# pneuBoard_rev3.net
KiCad netlist of a schematic drawn in EAGLE
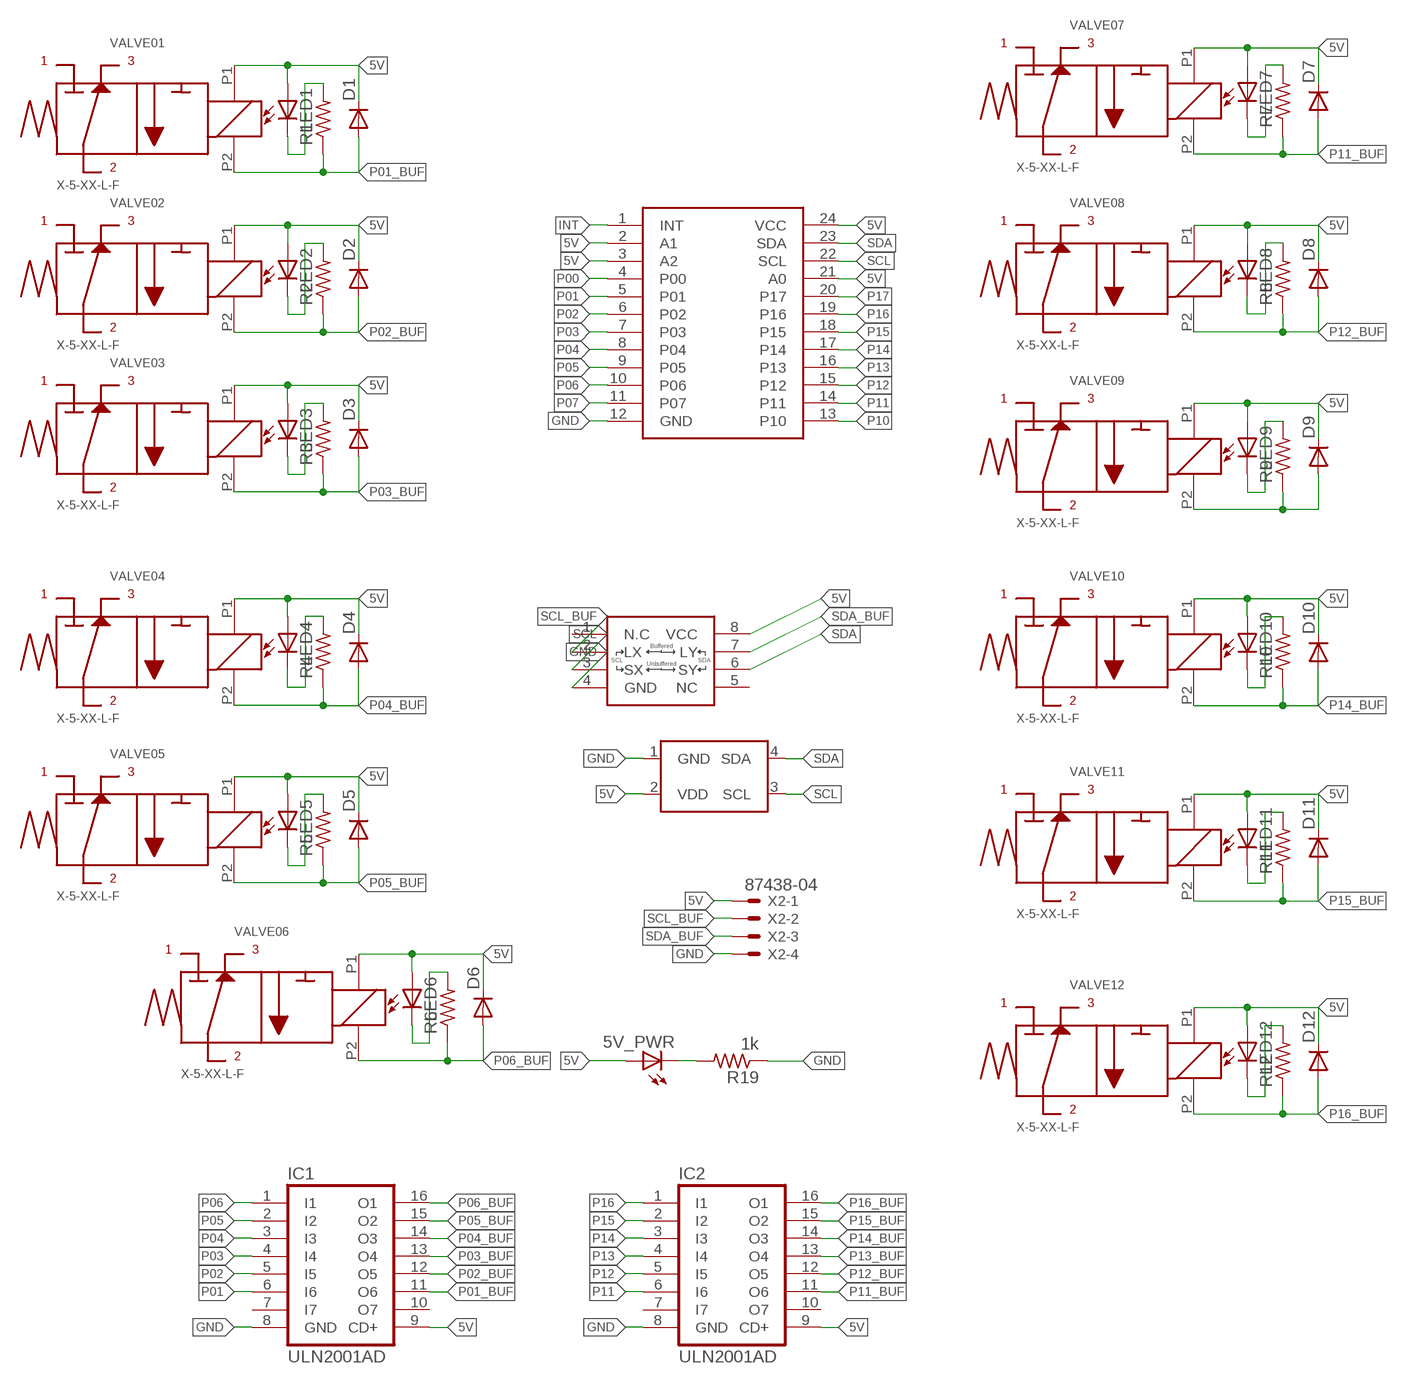
[diagram p0: schematic, sheet 1]

(export (version "E")
  (design (tool "Eeschema 10.0.6"))
  (components
    (comp (ref "5V_PWR")
      (value "LEDSML1206")
      (footprint "eagle-import:SML1206")
      (libsource (lib "eagle-import") (part "LEDSML1206"))
    )
    (comp (ref "D1")
      (value "DIODE-SOD123")
      (footprint "eagle-import:SOD123")
      (libsource (lib "eagle-import") (part "DIODE-SOD123"))
    )
    (comp (ref "D2")
      (value "DIODE-SOD123")
      (footprint "eagle-import:SOD123")
      (libsource (lib "eagle-import") (part "DIODE-SOD123"))
    )
    (comp (ref "D3")
      (value "DIODE-SOD123")
      (footprint "eagle-import:SOD123")
      (libsource (lib "eagle-import") (part "DIODE-SOD123"))
    )
    (comp (ref "D4")
      (value "DIODE-SOD123")
      (footprint "eagle-import:SOD123")
      (libsource (lib "eagle-import") (part "DIODE-SOD123"))
    )
    (comp (ref "D5")
      (value "DIODE-SOD123")
      (footprint "eagle-import:SOD123")
      (libsource (lib "eagle-import") (part "DIODE-SOD123"))
    )
    (comp (ref "D6")
      (value "DIODE-SOD123")
      (footprint "eagle-import:SOD123")
      (libsource (lib "eagle-import") (part "DIODE-SOD123"))
    )
    (comp (ref "D7")
      (value "DIODE-SOD123")
      (footprint "eagle-import:SOD123")
      (libsource (lib "eagle-import") (part "DIODE-SOD123"))
    )
    (comp (ref "D8")
      (value "DIODE-SOD123")
      (footprint "eagle-import:SOD123")
      (libsource (lib "eagle-import") (part "DIODE-SOD123"))
    )
    (comp (ref "D9")
      (value "DIODE-SOD123")
      (footprint "eagle-import:SOD123")
      (libsource (lib "eagle-import") (part "DIODE-SOD123"))
    )
    (comp (ref "D10")
      (value "DIODE-SOD123")
      (footprint "eagle-import:SOD123")
      (libsource (lib "eagle-import") (part "DIODE-SOD123"))
    )
    (comp (ref "D11")
      (value "DIODE-SOD123")
      (footprint "eagle-import:SOD123")
      (libsource (lib "eagle-import") (part "DIODE-SOD123"))
    )
    (comp (ref "D12")
      (value "DIODE-SOD123")
      (footprint "eagle-import:SOD123")
      (libsource (lib "eagle-import") (part "DIODE-SOD123"))
    )
    (comp (ref "IC1")
      (value "ULN2001AD")
      (footprint "eagle-import:SO16")
      (libsource (lib "eagle-import") (part "ULN2001AD"))
    )
    (comp (ref "IC2")
      (value "ULN2001AD")
      (footprint "eagle-import:SO16")
      (libsource (lib "eagle-import") (part "ULN2001AD"))
    )
    (comp (ref "LED1")
      (value "LEDCHIPLED_1206")
      (footprint "eagle-import:CHIPLED_1206")
      (libsource (lib "eagle-import") (part "LEDCHIPLED_1206"))
    )
    (comp (ref "LED2")
      (value "LEDCHIPLED_1206")
      (footprint "eagle-import:CHIPLED_1206")
      (libsource (lib "eagle-import") (part "LEDCHIPLED_1206"))
    )
    (comp (ref "LED3")
      (value "LEDCHIPLED_1206")
      (footprint "eagle-import:CHIPLED_1206")
      (libsource (lib "eagle-import") (part "LEDCHIPLED_1206"))
    )
    (comp (ref "LED4")
      (value "LEDCHIPLED_1206")
      (footprint "eagle-import:CHIPLED_1206")
      (libsource (lib "eagle-import") (part "LEDCHIPLED_1206"))
    )
    (comp (ref "LED5")
      (value "LEDCHIPLED_1206")
      (footprint "eagle-import:CHIPLED_1206")
      (libsource (lib "eagle-import") (part "LEDCHIPLED_1206"))
    )
    (comp (ref "LED6")
      (value "LEDCHIPLED_1206")
      (footprint "eagle-import:CHIPLED_1206")
      (libsource (lib "eagle-import") (part "LEDCHIPLED_1206"))
    )
    (comp (ref "LED7")
      (value "LEDCHIPLED_1206")
      (footprint "eagle-import:CHIPLED_1206")
      (libsource (lib "eagle-import") (part "LEDCHIPLED_1206"))
    )
    (comp (ref "LED8")
      (value "LEDCHIPLED_1206")
      (footprint "eagle-import:CHIPLED_1206")
      (libsource (lib "eagle-import") (part "LEDCHIPLED_1206"))
    )
    (comp (ref "LED9")
      (value "LEDCHIPLED_1206")
      (footprint "eagle-import:CHIPLED_1206")
      (libsource (lib "eagle-import") (part "LEDCHIPLED_1206"))
    )
    (comp (ref "LED10")
      (value "LEDCHIPLED_1206")
      (footprint "eagle-import:CHIPLED_1206")
      (libsource (lib "eagle-import") (part "LEDCHIPLED_1206"))
    )
    (comp (ref "LED11")
      (value "LEDCHIPLED_1206")
      (footprint "eagle-import:CHIPLED_1206")
      (libsource (lib "eagle-import") (part "LEDCHIPLED_1206"))
    )
    (comp (ref "LED12")
      (value "LEDCHIPLED_1206")
      (footprint "eagle-import:CHIPLED_1206")
      (libsource (lib "eagle-import") (part "LEDCHIPLED_1206"))
    )
    (comp (ref "R1")
      (value "R-US_R0603")
      (footprint "eagle-import:R0603")
      (libsource (lib "eagle-import") (part "R-US_R0603"))
    )
    (comp (ref "R2")
      (value "R-US_R0603")
      (footprint "eagle-import:R0603")
      (libsource (lib "eagle-import") (part "R-US_R0603"))
    )
    (comp (ref "R3")
      (value "R-US_R0603")
      (footprint "eagle-import:R0603")
      (libsource (lib "eagle-import") (part "R-US_R0603"))
    )
    (comp (ref "R4")
      (value "R-US_R0603")
      (footprint "eagle-import:R0603")
      (libsource (lib "eagle-import") (part "R-US_R0603"))
    )
    (comp (ref "R5")
      (value "R-US_R0603")
      (footprint "eagle-import:R0603")
      (libsource (lib "eagle-import") (part "R-US_R0603"))
    )
    (comp (ref "R6")
      (value "R-US_R0603")
      (footprint "eagle-import:R0603")
      (libsource (lib "eagle-import") (part "R-US_R0603"))
    )
    (comp (ref "R7")
      (value "R-US_R0603")
      (footprint "eagle-import:R0603")
      (libsource (lib "eagle-import") (part "R-US_R0603"))
    )
    (comp (ref "R8")
      (value "R-US_R0603")
      (footprint "eagle-import:R0603")
      (libsource (lib "eagle-import") (part "R-US_R0603"))
    )
    (comp (ref "R9")
      (value "R-US_R0603")
      (footprint "eagle-import:R0603")
      (libsource (lib "eagle-import") (part "R-US_R0603"))
    )
    (comp (ref "R10")
      (value "R-US_R0603")
      (footprint "eagle-import:R0603")
      (libsource (lib "eagle-import") (part "R-US_R0603"))
    )
    (comp (ref "R11")
      (value "R-US_R0603")
      (footprint "eagle-import:R0603")
      (libsource (lib "eagle-import") (part "R-US_R0603"))
    )
    (comp (ref "R12")
      (value "R-US_R0603")
      (footprint "eagle-import:R0603")
      (libsource (lib "eagle-import") (part "R-US_R0603"))
    )
    (comp (ref "R19")
      (value "1k")
      (footprint "eagle-import:R0603")
      (libsource (lib "eagle-import") (part "R-US_R0603"))
    )
    (comp (ref "U$1")
      (value "PCF8575C")
      (footprint "eagle-import:PW_R-PDSO-G24")
      (libsource (lib "eagle-import") (part "PCF8575C"))
    )
    (comp (ref "U$2")
      (value "P82B715")
      (footprint "eagle-import:SO8")
      (libsource (lib "eagle-import") (part "P82B715"))
    )
    (comp (ref "U$3")
      (value "MS5837-30BA")
      (footprint "eagle-import:MS5837-30BA")
      (libsource (lib "eagle-import") (part "MS5837-30BA"))
    )
    (comp (ref "VALVE01")
      (value "X-5-XX-L-F")
      (footprint "eagle-import:X-SERIES")
      (libsource (lib "eagle-import") (part "X-5-XX-L-F"))
    )
    (comp (ref "VALVE02")
      (value "X-5-XX-L-F")
      (footprint "eagle-import:X-SERIES")
      (libsource (lib "eagle-import") (part "X-5-XX-L-F"))
    )
    (comp (ref "VALVE03")
      (value "X-5-XX-L-F")
      (footprint "eagle-import:X-SERIES")
      (libsource (lib "eagle-import") (part "X-5-XX-L-F"))
    )
    (comp (ref "VALVE04")
      (value "X-5-XX-L-F")
      (footprint "eagle-import:X-SERIES")
      (libsource (lib "eagle-import") (part "X-5-XX-L-F"))
    )
    (comp (ref "VALVE05")
      (value "X-5-XX-L-F")
      (footprint "eagle-import:X-SERIES")
      (libsource (lib "eagle-import") (part "X-5-XX-L-F"))
    )
    (comp (ref "VALVE06")
      (value "X-5-XX-L-F")
      (footprint "eagle-import:X-SERIES")
      (libsource (lib "eagle-import") (part "X-5-XX-L-F"))
    )
    (comp (ref "VALVE07")
      (value "X-5-XX-L-F")
      (footprint "eagle-import:X-SERIES")
      (libsource (lib "eagle-import") (part "X-5-XX-L-F"))
    )
    (comp (ref "VALVE08")
      (value "X-5-XX-L-F")
      (footprint "eagle-import:X-SERIES")
      (libsource (lib "eagle-import") (part "X-5-XX-L-F"))
    )
    (comp (ref "VALVE09")
      (value "X-5-XX-L-F")
      (footprint "eagle-import:X-SERIES")
      (libsource (lib "eagle-import") (part "X-5-XX-L-F"))
    )
    (comp (ref "VALVE10")
      (value "X-5-XX-L-F")
      (footprint "eagle-import:X-SERIES")
      (libsource (lib "eagle-import") (part "X-5-XX-L-F"))
    )
    (comp (ref "VALVE11")
      (value "X-5-XX-L-F")
      (footprint "eagle-import:X-SERIES")
      (libsource (lib "eagle-import") (part "X-5-XX-L-F"))
    )
    (comp (ref "VALVE12")
      (value "X-5-XX-L-F")
      (footprint "eagle-import:X-SERIES")
      (libsource (lib "eagle-import") (part "X-5-XX-L-F"))
    )
    (comp (ref "X2")
      (value "87438-04")
      (footprint "eagle-import:87438-04")
      (libsource (lib "eagle-import") (part "87438-04"))
    )
  )
  (nets
    (net (code "1") (name "5V") (class "Default")
      (node (ref "5V_PWR") (pin "A") (pinfunction "A_A") (pintype "passive"))
      (node (ref "D1") (pin "C") (pinfunction "C_C") (pintype "passive"))
      (node (ref "D10") (pin "C") (pinfunction "C_C") (pintype "passive"))
      (node (ref "D11") (pin "C") (pinfunction "C_C") (pintype "passive"))
      (node (ref "D12") (pin "C") (pinfunction "C_C") (pintype "passive"))
      (node (ref "D2") (pin "C") (pinfunction "C_C") (pintype "passive"))
      (node (ref "D3") (pin "C") (pinfunction "C_C") (pintype "passive"))
      (node (ref "D4") (pin "C") (pinfunction "C_C") (pintype "passive"))
      (node (ref "D5") (pin "C") (pinfunction "C_C") (pintype "passive"))
      (node (ref "D6") (pin "C") (pinfunction "C_C") (pintype "passive"))
      (node (ref "D7") (pin "C") (pinfunction "C_C") (pintype "passive"))
      (node (ref "D8") (pin "C") (pinfunction "C_C") (pintype "passive"))
      (node (ref "D9") (pin "C") (pinfunction "C_C") (pintype "passive"))
      (node (ref "IC1") (pin "9") (pinfunction "CD+_9") (pintype "passive"))
      (node (ref "IC2") (pin "9") (pinfunction "CD+_9") (pintype "passive"))
      (node (ref "LED1") (pin "A") (pinfunction "A_A") (pintype "passive"))
      (node (ref "LED10") (pin "A") (pinfunction "A_A") (pintype "passive"))
      (node (ref "LED11") (pin "A") (pinfunction "A_A") (pintype "passive"))
      (node (ref "LED12") (pin "A") (pinfunction "A_A") (pintype "passive"))
      (node (ref "LED2") (pin "A") (pinfunction "A_A") (pintype "passive"))
      (node (ref "LED3") (pin "A") (pinfunction "A_A") (pintype "passive"))
      (node (ref "LED4") (pin "A") (pinfunction "A_A") (pintype "passive"))
      (node (ref "LED5") (pin "A") (pinfunction "A_A") (pintype "passive"))
      (node (ref "LED6") (pin "A") (pinfunction "A_A") (pintype "passive"))
      (node (ref "LED7") (pin "A") (pinfunction "A_A") (pintype "passive"))
      (node (ref "LED8") (pin "A") (pinfunction "A_A") (pintype "passive"))
      (node (ref "LED9") (pin "A") (pinfunction "A_A") (pintype "passive"))
      (node (ref "U$1") (pin "2") (pinfunction "A1_2") (pintype "bidirectional"))
      (node (ref "U$1") (pin "21") (pinfunction "A0_21") (pintype "bidirectional"))
      (node (ref "U$1") (pin "24") (pinfunction "VCC_24") (pintype "bidirectional"))
      (node (ref "U$1") (pin "3") (pinfunction "A2_3") (pintype "bidirectional"))
      (node (ref "U$2") (pin "8") (pinfunction "VCC_8") (pintype "bidirectional"))
      (node (ref "U$3") (pin "2") (pinfunction "VDD_2") (pintype "bidirectional"))
      (node (ref "VALVE01") (pin "P1") (pinfunction "1_P1") (pintype "bidirectional"))
      (node (ref "VALVE02") (pin "P1") (pinfunction "1_P1") (pintype "bidirectional"))
      (node (ref "VALVE03") (pin "P1") (pinfunction "1_P1") (pintype "bidirectional"))
      (node (ref "VALVE04") (pin "P1") (pinfunction "1_P1") (pintype "bidirectional"))
      (node (ref "VALVE05") (pin "P1") (pinfunction "1_P1") (pintype "bidirectional"))
      (node (ref "VALVE06") (pin "P1") (pinfunction "1_P1") (pintype "bidirectional"))
      (node (ref "VALVE07") (pin "P1") (pinfunction "1_P1") (pintype "bidirectional"))
      (node (ref "VALVE08") (pin "P1") (pinfunction "1_P1") (pintype "bidirectional"))
      (node (ref "VALVE09") (pin "P1") (pinfunction "1_P1") (pintype "bidirectional"))
      (node (ref "VALVE10") (pin "P1") (pinfunction "1_P1") (pintype "bidirectional"))
      (node (ref "VALVE11") (pin "P1") (pinfunction "1_P1") (pintype "bidirectional"))
      (node (ref "VALVE12") (pin "P1") (pinfunction "1_P1") (pintype "bidirectional"))
      (node (ref "X2") (pin "1") (pinfunction "S_1") (pintype "passive"))
    )
    (net (code "2") (name "GND") (class "Default")
      (node (ref "IC1") (pin "8") (pinfunction "GND_8") (pintype "power_in"))
      (node (ref "IC2") (pin "8") (pinfunction "GND_8") (pintype "power_in"))
      (node (ref "R19") (pin "1") (pinfunction "1_1") (pintype "passive"))
      (node (ref "U$1") (pin "12") (pinfunction "GND_12") (pintype "bidirectional"))
      (node (ref "U$2") (pin "4") (pinfunction "GND_4") (pintype "bidirectional"))
      (node (ref "U$3") (pin "1") (pinfunction "GND_1") (pintype "bidirectional"))
      (node (ref "X2") (pin "4") (pinfunction "S_4") (pintype "passive"))
    )
    (net (code "3") (name "INT") (class "Default")
      (node (ref "U$1") (pin "1") (pinfunction "INT_1") (pintype "bidirectional"))
    )
    (net (code "4") (name "Net-(5V_PWR-PadC)") (class "Default")
      (node (ref "5V_PWR") (pin "C") (pinfunction "C_C") (pintype "passive"))
      (node (ref "R19") (pin "2") (pinfunction "2_2") (pintype "passive"))
    )
    (net (code "5") (name "Net-(LED1-PadC)") (class "Default")
      (node (ref "LED1") (pin "C") (pinfunction "C_C") (pintype "passive"))
      (node (ref "R1") (pin "2") (pinfunction "2_2") (pintype "passive"))
    )
    (net (code "6") (name "Net-(LED2-PadC)") (class "Default")
      (node (ref "LED2") (pin "C") (pinfunction "C_C") (pintype "passive"))
      (node (ref "R2") (pin "2") (pinfunction "2_2") (pintype "passive"))
    )
    (net (code "7") (name "Net-(LED3-PadC)") (class "Default")
      (node (ref "LED3") (pin "C") (pinfunction "C_C") (pintype "passive"))
      (node (ref "R3") (pin "2") (pinfunction "2_2") (pintype "passive"))
    )
    (net (code "8") (name "Net-(LED4-PadC)") (class "Default")
      (node (ref "LED4") (pin "C") (pinfunction "C_C") (pintype "passive"))
      (node (ref "R4") (pin "2") (pinfunction "2_2") (pintype "passive"))
    )
    (net (code "9") (name "Net-(LED5-PadC)") (class "Default")
      (node (ref "LED5") (pin "C") (pinfunction "C_C") (pintype "passive"))
      (node (ref "R5") (pin "2") (pinfunction "2_2") (pintype "passive"))
    )
    (net (code "10") (name "Net-(LED6-PadC)") (class "Default")
      (node (ref "LED6") (pin "C") (pinfunction "C_C") (pintype "passive"))
      (node (ref "R6") (pin "2") (pinfunction "2_2") (pintype "passive"))
    )
    (net (code "11") (name "Net-(LED7-PadC)") (class "Default")
      (node (ref "LED7") (pin "C") (pinfunction "C_C") (pintype "passive"))
      (node (ref "R7") (pin "2") (pinfunction "2_2") (pintype "passive"))
    )
    (net (code "12") (name "Net-(LED8-PadC)") (class "Default")
      (node (ref "LED8") (pin "C") (pinfunction "C_C") (pintype "passive"))
      (node (ref "R8") (pin "2") (pinfunction "2_2") (pintype "passive"))
    )
    (net (code "13") (name "Net-(LED9-PadC)") (class "Default")
      (node (ref "LED9") (pin "C") (pinfunction "C_C") (pintype "passive"))
      (node (ref "R9") (pin "2") (pinfunction "2_2") (pintype "passive"))
    )
    (net (code "14") (name "Net-(LED10-PadC)") (class "Default")
      (node (ref "LED10") (pin "C") (pinfunction "C_C") (pintype "passive"))
      (node (ref "R10") (pin "2") (pinfunction "2_2") (pintype "passive"))
    )
    (net (code "15") (name "Net-(LED11-PadC)") (class "Default")
      (node (ref "LED11") (pin "C") (pinfunction "C_C") (pintype "passive"))
      (node (ref "R11") (pin "2") (pinfunction "2_2") (pintype "passive"))
    )
    (net (code "16") (name "Net-(LED12-PadC)") (class "Default")
      (node (ref "LED12") (pin "C") (pinfunction "C_C") (pintype "passive"))
      (node (ref "R12") (pin "2") (pinfunction "2_2") (pintype "passive"))
    )
    (net (code "17") (name "P00") (class "Default")
      (node (ref "U$1") (pin "4") (pinfunction "P00_4") (pintype "bidirectional"))
    )
    (net (code "18") (name "P01") (class "Default")
      (node (ref "IC1") (pin "6") (pinfunction "I6_6") (pintype "input"))
      (node (ref "U$1") (pin "5") (pinfunction "P01_5") (pintype "bidirectional"))
    )
    (net (code "19") (name "P01_BUF") (class "Default")
      (node (ref "D1") (pin "A") (pinfunction "A_A") (pintype "passive"))
      (node (ref "IC1") (pin "11") (pinfunction "O6_11") (pintype "open_collector"))
      (node (ref "R1") (pin "1") (pinfunction "1_1") (pintype "passive"))
      (node (ref "VALVE01") (pin "P2") (pinfunction "2_P2") (pintype "bidirectional"))
    )
    (net (code "20") (name "P02") (class "Default")
      (node (ref "IC1") (pin "5") (pinfunction "I5_5") (pintype "input"))
      (node (ref "U$1") (pin "6") (pinfunction "P02_6") (pintype "bidirectional"))
    )
    (net (code "21") (name "P02_BUF") (class "Default")
      (node (ref "D2") (pin "A") (pinfunction "A_A") (pintype "passive"))
      (node (ref "IC1") (pin "12") (pinfunction "O5_12") (pintype "open_collector"))
      (node (ref "R2") (pin "1") (pinfunction "1_1") (pintype "passive"))
      (node (ref "VALVE02") (pin "P2") (pinfunction "2_P2") (pintype "bidirectional"))
    )
    (net (code "22") (name "P03") (class "Default")
      (node (ref "IC1") (pin "4") (pinfunction "I4_4") (pintype "input"))
      (node (ref "U$1") (pin "7") (pinfunction "P03_7") (pintype "bidirectional"))
    )
    (net (code "23") (name "P03_BUF") (class "Default")
      (node (ref "D3") (pin "A") (pinfunction "A_A") (pintype "passive"))
      (node (ref "IC1") (pin "13") (pinfunction "O4_13") (pintype "open_collector"))
      (node (ref "R3") (pin "1") (pinfunction "1_1") (pintype "passive"))
      (node (ref "VALVE03") (pin "P2") (pinfunction "2_P2") (pintype "bidirectional"))
    )
    (net (code "24") (name "P04") (class "Default")
      (node (ref "IC1") (pin "3") (pinfunction "I3_3") (pintype "input"))
      (node (ref "U$1") (pin "8") (pinfunction "P04_8") (pintype "bidirectional"))
    )
    (net (code "25") (name "P04_BUF") (class "Default")
      (node (ref "D4") (pin "A") (pinfunction "A_A") (pintype "passive"))
      (node (ref "IC1") (pin "14") (pinfunction "O3_14") (pintype "open_collector"))
      (node (ref "R4") (pin "1") (pinfunction "1_1") (pintype "passive"))
      (node (ref "VALVE04") (pin "P2") (pinfunction "2_P2") (pintype "bidirectional"))
    )
    (net (code "26") (name "P05") (class "Default")
      (node (ref "IC1") (pin "2") (pinfunction "I2_2") (pintype "input"))
      (node (ref "U$1") (pin "9") (pinfunction "P05_9") (pintype "bidirectional"))
    )
    (net (code "27") (name "P05_BUF") (class "Default")
      (node (ref "D5") (pin "A") (pinfunction "A_A") (pintype "passive"))
      (node (ref "IC1") (pin "15") (pinfunction "O2_15") (pintype "open_collector"))
      (node (ref "R5") (pin "1") (pinfunction "1_1") (pintype "passive"))
      (node (ref "VALVE05") (pin "P2") (pinfunction "2_P2") (pintype "bidirectional"))
    )
    (net (code "28") (name "P06") (class "Default")
      (node (ref "IC1") (pin "1") (pinfunction "I1_1") (pintype "input"))
      (node (ref "U$1") (pin "10") (pinfunction "P06_10") (pintype "bidirectional"))
    )
    (net (code "29") (name "P06_BUF") (class "Default")
      (node (ref "D6") (pin "A") (pinfunction "A_A") (pintype "passive"))
      (node (ref "IC1") (pin "16") (pinfunction "O1_16") (pintype "open_collector"))
      (node (ref "R6") (pin "1") (pinfunction "1_1") (pintype "passive"))
      (node (ref "VALVE06") (pin "P2") (pinfunction "2_P2") (pintype "bidirectional"))
    )
    (net (code "30") (name "P07") (class "Default")
      (node (ref "U$1") (pin "11") (pinfunction "P07_11") (pintype "bidirectional"))
    )
    (net (code "31") (name "P10") (class "Default")
      (node (ref "U$1") (pin "13") (pinfunction "P10_13") (pintype "bidirectional"))
    )
    (net (code "32") (name "P11") (class "Default")
      (node (ref "IC2") (pin "6") (pinfunction "I6_6") (pintype "input"))
      (node (ref "U$1") (pin "14") (pinfunction "P11_14") (pintype "bidirectional"))
    )
    (net (code "33") (name "P11_BUF") (class "Default")
      (node (ref "D7") (pin "A") (pinfunction "A_A") (pintype "passive"))
      (node (ref "IC2") (pin "11") (pinfunction "O6_11") (pintype "open_collector"))
      (node (ref "R7") (pin "1") (pinfunction "1_1") (pintype "passive"))
      (node (ref "VALVE07") (pin "P2") (pinfunction "2_P2") (pintype "bidirectional"))
    )
    (net (code "34") (name "P12") (class "Default")
      (node (ref "IC2") (pin "5") (pinfunction "I5_5") (pintype "input"))
      (node (ref "U$1") (pin "15") (pinfunction "P12_15") (pintype "bidirectional"))
    )
    (net (code "35") (name "P12_BUF") (class "Default")
      (node (ref "D8") (pin "A") (pinfunction "A_A") (pintype "passive"))
      (node (ref "IC2") (pin "12") (pinfunction "O5_12") (pintype "open_collector"))
      (node (ref "R8") (pin "1") (pinfunction "1_1") (pintype "passive"))
      (node (ref "VALVE08") (pin "P2") (pinfunction "2_P2") (pintype "bidirectional"))
    )
    (net (code "36") (name "P13") (class "Default")
      (node (ref "IC2") (pin "4") (pinfunction "I4_4") (pintype "input"))
      (node (ref "U$1") (pin "16") (pinfunction "P13_16") (pintype "bidirectional"))
    )
    (net (code "37") (name "P13_BUF") (class "Default")
      (node (ref "D9") (pin "A") (pinfunction "A_A") (pintype "passive"))
      (node (ref "IC2") (pin "13") (pinfunction "O4_13") (pintype "open_collector"))
      (node (ref "R9") (pin "1") (pinfunction "1_1") (pintype "passive"))
      (node (ref "VALVE09") (pin "P2") (pinfunction "2_P2") (pintype "bidirectional"))
    )
    (net (code "38") (name "P14") (class "Default")
      (node (ref "IC2") (pin "3") (pinfunction "I3_3") (pintype "input"))
      (node (ref "U$1") (pin "17") (pinfunction "P14_17") (pintype "bidirectional"))
    )
    (net (code "39") (name "P14_BUF") (class "Default")
      (node (ref "D10") (pin "A") (pinfunction "A_A") (pintype "passive"))
      (node (ref "IC2") (pin "14") (pinfunction "O3_14") (pintype "open_collector"))
      (node (ref "R10") (pin "1") (pinfunction "1_1") (pintype "passive"))
      (node (ref "VALVE10") (pin "P2") (pinfunction "2_P2") (pintype "bidirectional"))
    )
    (net (code "40") (name "P15") (class "Default")
      (node (ref "IC2") (pin "2") (pinfunction "I2_2") (pintype "input"))
      (node (ref "U$1") (pin "18") (pinfunction "P15_18") (pintype "bidirectional"))
    )
    (net (code "41") (name "P15_BUF") (class "Default")
      (node (ref "D11") (pin "A") (pinfunction "A_A") (pintype "passive"))
      (node (ref "IC2") (pin "15") (pinfunction "O2_15") (pintype "open_collector"))
      (node (ref "R11") (pin "1") (pinfunction "1_1") (pintype "passive"))
      (node (ref "VALVE11") (pin "P2") (pinfunction "2_P2") (pintype "bidirectional"))
    )
    (net (code "42") (name "P16") (class "Default")
      (node (ref "IC2") (pin "1") (pinfunction "I1_1") (pintype "input"))
      (node (ref "U$1") (pin "19") (pinfunction "P16_19") (pintype "bidirectional"))
    )
    (net (code "43") (name "P16_BUF") (class "Default")
      (node (ref "D12") (pin "A") (pinfunction "A_A") (pintype "passive"))
      (node (ref "IC2") (pin "16") (pinfunction "O1_16") (pintype "open_collector"))
      (node (ref "R12") (pin "1") (pinfunction "1_1") (pintype "passive"))
      (node (ref "VALVE12") (pin "P2") (pinfunction "2_P2") (pintype "bidirectional"))
    )
    (net (code "44") (name "P17") (class "Default")
      (node (ref "U$1") (pin "20") (pinfunction "P17_20") (pintype "bidirectional"))
    )
    (net (code "45") (name "SCL") (class "Default")
      (node (ref "U$1") (pin "22") (pinfunction "SCL_22") (pintype "bidirectional"))
      (node (ref "U$2") (pin "3") (pinfunction "SX_3") (pintype "bidirectional"))
      (node (ref "U$3") (pin "3") (pinfunction "SCL_3") (pintype "bidirectional"))
    )
    (net (code "46") (name "SCL_BUF") (class "Default")
      (node (ref "U$2") (pin "2") (pinfunction "LX_2") (pintype "bidirectional"))
      (node (ref "X2") (pin "2") (pinfunction "S_2") (pintype "passive"))
    )
    (net (code "47") (name "SDA") (class "Default")
      (node (ref "U$1") (pin "23") (pinfunction "SDA_23") (pintype "bidirectional"))
      (node (ref "U$2") (pin "6") (pinfunction "SY_6") (pintype "bidirectional"))
      (node (ref "U$3") (pin "4") (pinfunction "SDA_4") (pintype "bidirectional"))
    )
    (net (code "48") (name "SDA_BUF") (class "Default")
      (node (ref "U$2") (pin "7") (pinfunction "LY_7") (pintype "bidirectional"))
      (node (ref "X2") (pin "3") (pinfunction "S_3") (pintype "passive"))
    )
    (net (code "49") (name "unconnected-(IC1-I7-Pad7)") (class "Default")
      (node (ref "IC1") (pin "7") (pinfunction "I7_7") (pintype "input"))
    )
    (net (code "50") (name "unconnected-(IC1-O7-Pad10)") (class "Default")
      (node (ref "IC1") (pin "10") (pinfunction "O7_10") (pintype "open_collector"))
    )
    (net (code "51") (name "unconnected-(IC2-I7-Pad7)") (class "Default")
      (node (ref "IC2") (pin "7") (pinfunction "I7_7") (pintype "input"))
    )
    (net (code "52") (name "unconnected-(IC2-O7-Pad10)") (class "Default")
      (node (ref "IC2") (pin "10") (pinfunction "O7_10") (pintype "open_collector"))
    )
    (net (code "53") (name "unconnected-(U$2-N.C-Pad1)") (class "Default")
      (node (ref "U$2") (pin "1") (pinfunction "N.C_1") (pintype "bidirectional"))
    )
    (net (code "54") (name "unconnected-(U$2-NC-Pad5)") (class "Default")
      (node (ref "U$2") (pin "5") (pinfunction "NC_5") (pintype "bidirectional"))
    )
  )
)
